# STM32F103C8T6_Coreboard.net
KiCad netlist of a schematic drawn in Altium Designer
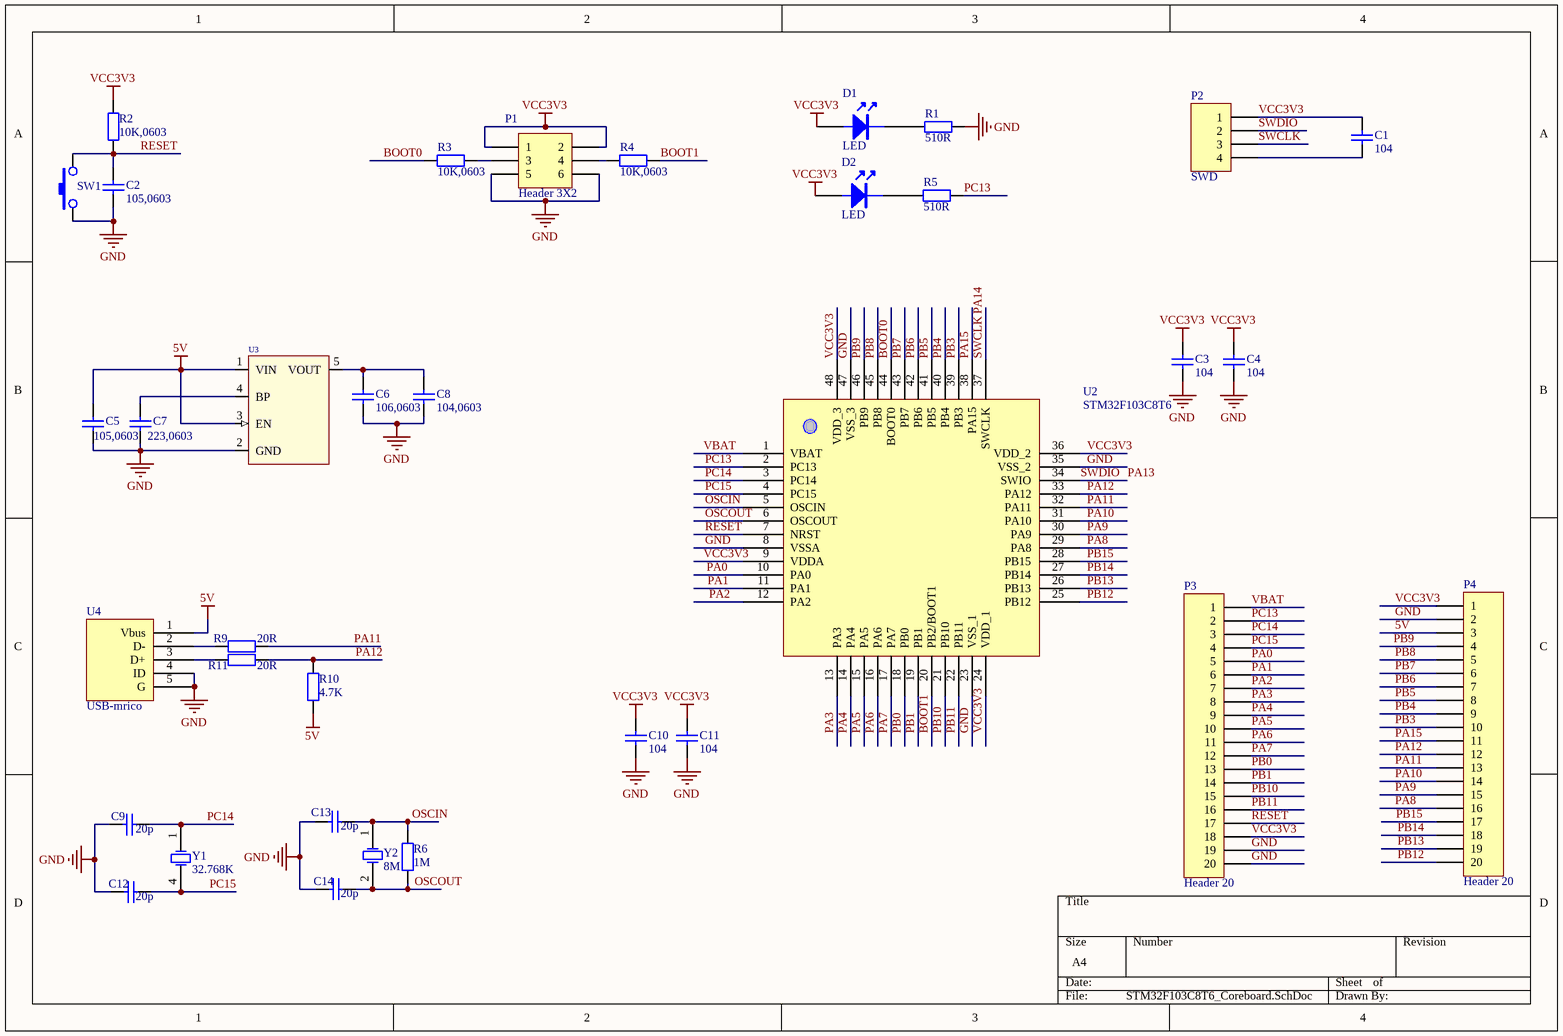
[diagram p0: STM32F103C8T6_Coreboard.SchDoc]

(export (version "E")
  (design (tool "Eeschema 10.0.6"))
  (components
    (comp (ref "C1")
      (value "104")
      (footprint "C0603")
      (description "Capacitor")
      (fields (field (name "PUBLISHER") "Altium Limited"))
      (libsource (lib "STM32F103C8T6_Coreboard") (part "Cap"))
    )
    (comp (ref "C2")
      (value "105,0603")
      (footprint "C0603")
      (description "Capacitor")
      (fields (field (name "PUBLISHER") "Altium Limited"))
      (libsource (lib "STM32F103C8T6_Coreboard") (part "Cap"))
    )
    (comp (ref "C3")
      (value "104")
      (footprint "C0603")
      (description "Capacitor")
      (fields (field (name "PUBLISHER") "Altium Limited"))
      (libsource (lib "STM32F103C8T6_Coreboard") (part "Cap"))
    )
    (comp (ref "C4")
      (value "104")
      (footprint "C0603")
      (description "Capacitor")
      (fields (field (name "PUBLISHER") "Altium Limited"))
      (libsource (lib "STM32F103C8T6_Coreboard") (part "Cap"))
    )
    (comp (ref "C5")
      (value "105,0603")
      (footprint "C0603")
      (description "Capacitor")
      (fields (field (name "PUBLISHER") "Altium Limited"))
      (libsource (lib "STM32F103C8T6_Coreboard") (part "Cap"))
    )
    (comp (ref "C6")
      (value "106,0603")
      (footprint "C0603")
      (description "Capacitor")
      (fields (field (name "PUBLISHER") "Altium Limited"))
      (libsource (lib "STM32F103C8T6_Coreboard") (part "Cap"))
    )
    (comp (ref "C7")
      (value "223,0603")
      (footprint "C0603")
      (description "Capacitor")
      (fields (field (name "PUBLISHER") "Altium Limited"))
      (libsource (lib "STM32F103C8T6_Coreboard") (part "Cap"))
    )
    (comp (ref "C8")
      (value "104,0603")
      (footprint "C0603")
      (description "Capacitor")
      (fields (field (name "PUBLISHER") "Altium Limited"))
      (libsource (lib "STM32F103C8T6_Coreboard") (part "Cap"))
    )
    (comp (ref "C9")
      (value "20p")
      (footprint "C0603")
      (description "Capacitor")
      (fields (field (name "PUBLISHER") "Altium Limited"))
      (libsource (lib "STM32F103C8T6_Coreboard") (part "Cap"))
    )
    (comp (ref "C10")
      (value "104")
      (footprint "C0603")
      (description "Capacitor")
      (fields (field (name "PUBLISHER") "Altium Limited"))
      (libsource (lib "STM32F103C8T6_Coreboard") (part "Cap"))
    )
    (comp (ref "C11")
      (value "104")
      (footprint "C0603")
      (description "Capacitor")
      (fields (field (name "PUBLISHER") "Altium Limited"))
      (libsource (lib "STM32F103C8T6_Coreboard") (part "Cap"))
    )
    (comp (ref "C12")
      (value "20p")
      (footprint "C0603")
      (description "Capacitor")
      (fields (field (name "PUBLISHER") "Altium Limited"))
      (libsource (lib "STM32F103C8T6_Coreboard") (part "Cap"))
    )
    (comp (ref "C13")
      (value "20p")
      (footprint "C0603")
      (description "Capacitor")
      (fields (field (name "PUBLISHER") "Altium Limited"))
      (libsource (lib "STM32F103C8T6_Coreboard") (part "Cap"))
    )
    (comp (ref "C14")
      (value "20p")
      (footprint "C0603")
      (description "Capacitor")
      (fields (field (name "PUBLISHER") "Altium Limited"))
      (libsource (lib "STM32F103C8T6_Coreboard") (part "Cap"))
    )
    (comp (ref "D1") (value "LED") (footprint "LED") (libsource (lib "STM32F103C8T6_Coreboard") (part "LED")))
    (comp (ref "D2") (value "LED") (footprint "LED") (libsource (lib "STM32F103C8T6_Coreboard") (part "LED")))
    (comp (ref "P1")
      (value "Header 3X2")
      (footprint "HDR2X3")
      (description "Header, 3-Pin, Dual row")
      (fields (field (name "PUBLISHER") "Altium Limited"))
      (libsource (lib "STM32F103C8T6_Coreboard") (part "Header 3X2"))
    )
    (comp (ref "P2")
      (value "SWD")
      (footprint "HDR1X4H")
      (description "Header, 4-Pin")
      (fields (field (name "PUBLISHER") "Altium Limited"))
      (libsource (lib "STM32F103C8T6_Coreboard") (part "Header 4"))
    )
    (comp (ref "P3")
      (value "Header 20")
      (footprint "HDR1X20")
      (description "Header, 20-Pin")
      (fields (field (name "PUBLISHER") "Altium Limited"))
      (libsource (lib "") (part "Header 20_1"))
    )
    (comp (ref "P4")
      (value "Header 20")
      (footprint "HDR1X20")
      (description "Header, 20-Pin")
      (fields (field (name "PUBLISHER") "Altium Limited"))
      (libsource (lib "STM32F103C8T6_Coreboard") (part "Header 20"))
    )
    (comp (ref "R1")
      (value "510R")
      (footprint "R0603")
      (description "Resistor")
      (fields (field (name "PUBLISHER") "Altium Limited"))
      (libsource (lib "STM32F103C8T6_Coreboard") (part "Res2"))
    )
    (comp (ref "R2")
      (value "10K,0603")
      (footprint "R0603")
      (description "Resistor")
      (fields (field (name "PUBLISHER") "Altium Limited"))
      (libsource (lib "") (part "Res2_1"))
    )
    (comp (ref "R3")
      (value "10K,0603")
      (footprint "R0603")
      (description "Resistor")
      (fields (field (name "PUBLISHER") "Altium Limited"))
      (libsource (lib "STM32F103C8T6_Coreboard") (part "Res2"))
    )
    (comp (ref "R4")
      (value "10K,0603")
      (footprint "R0603")
      (description "Resistor")
      (fields (field (name "PUBLISHER") "Altium Limited"))
      (libsource (lib "STM32F103C8T6_Coreboard") (part "Res2"))
    )
    (comp (ref "R5")
      (value "510R")
      (footprint "R0603")
      (description "Resistor")
      (fields (field (name "PUBLISHER") "Altium Limited"))
      (libsource (lib "STM32F103C8T6_Coreboard") (part "Res2"))
    )
    (comp (ref "R6")
      (value "1M")
      (footprint "R0603")
      (description "Resistor")
      (fields (field (name "PUBLISHER") "Altium Limited"))
      (libsource (lib "") (part "Res2_1"))
    )
    (comp (ref "R9")
      (value "20R")
      (footprint "R0603")
      (description "Resistor")
      (fields (field (name "PUBLISHER") "Altium Limited"))
      (libsource (lib "STM32F103C8T6_Coreboard") (part "Res2"))
    )
    (comp (ref "R10")
      (value "4.7K")
      (footprint "R0603")
      (description "Resistor")
      (fields (field (name "PUBLISHER") "Altium Limited"))
      (libsource (lib "") (part "Res2_1"))
    )
    (comp (ref "R11")
      (value "20R")
      (footprint "R0603")
      (description "Resistor")
      (fields (field (name "PUBLISHER") "Altium Limited"))
      (libsource (lib "STM32F103C8T6_Coreboard") (part "Res2"))
    )
    (comp (ref "SW1")
      (value "SW-PB_V")
      (footprint "KEY-SMT")
      (description "SWITCH")
      (libsource (lib "STM32F103C8T6_Coreboard") (part "SW-PB_V"))
    )
    (comp (ref "U2")
      (value "STM32F103C8T6")
      (footprint "48P")
      (libsource (lib "STM32F103C8T6_Coreboard") (part "STM32F103C8T6"))
    )
    (comp (ref "U3")
      (value "RT9193")
      (fields (field (name "ICA_PARTNUM") "$$2191094$$RT9193-15CU5") (field (name "PART NUMBER") "TMP-13"))
      (libsource (lib "STM32F103C8T6_Coreboard") (part "RT9193X_5P"))
    )
    (comp (ref "U4")
      (value "USB-mrico")
      (footprint "Micro_USB")
      (libsource (lib "STM32F103C8T6_Coreboard") (part "usb-STM"))
    )
    (comp (ref "Y1")
      (value "32.768K")
      (footprint "MC-306")
      (description "Crystal Oscillator")
      (fields (field (name "PUBLISHER") "Altium Limited"))
      (libsource (lib "STM32F103C8T6_Coreboard") (part "XTAL"))
    )
    (comp (ref "Y2")
      (value "8M")
      (footprint "XTAL1")
      (description "Crystal Oscillator")
      (fields (field (name "PUBLISHER") "Altium Limited"))
      (libsource (lib "STM32F103C8T6_Coreboard") (part "XTAL1"))
    )
  )
  (nets
    (net (code "1") (name "/BOOT0") (class "Default")
      (node (ref "R3") (pin "1") (pinfunction "1_1") (pintype "passive"))
      (node (ref "U2") (pin "44") (pinfunction "BOOT0_44") (pintype "passive"))
    )
    (net (code "2") (name "/BOOT1") (class "Default")
      (node (ref "R4") (pin "2") (pinfunction "2_2") (pintype "passive"))
      (node (ref "U2") (pin "20") (pinfunction "PB2/BOOT1_20") (pintype "passive"))
    )
    (net (code "3") (name "/OSCIN") (class "Default")
      (node (ref "C13") (pin "2") (pinfunction "2_2") (pintype "passive"))
      (node (ref "R6") (pin "2") (pinfunction "2_2") (pintype "passive"))
      (node (ref "U2") (pin "5") (pinfunction "OSCIN_5") (pintype "passive"))
      (node (ref "Y2") (pin "1") (pinfunction "OSC1_1") (pintype "passive"))
    )
    (net (code "4") (name "/OSCOUT") (class "Default")
      (node (ref "C14") (pin "2") (pinfunction "2_2") (pintype "passive"))
      (node (ref "R6") (pin "1") (pinfunction "1_1") (pintype "passive"))
      (node (ref "U2") (pin "6") (pinfunction "OSCOUT_6") (pintype "passive"))
      (node (ref "Y2") (pin "2") (pinfunction "OSC2_2") (pintype "passive"))
    )
    (net (code "5") (name "/PA0") (class "Default")
      (node (ref "P3") (pin "5") (pinfunction "5_5") (pintype "passive"))
      (node (ref "U2") (pin "10") (pinfunction "PA0_10") (pintype "passive"))
    )
    (net (code "6") (name "/PA1") (class "Default")
      (node (ref "P3") (pin "6") (pinfunction "6_6") (pintype "passive"))
      (node (ref "U2") (pin "11") (pinfunction "PA1_11") (pintype "passive"))
    )
    (net (code "7") (name "/PA2") (class "Default")
      (node (ref "P3") (pin "7") (pinfunction "7_7") (pintype "passive"))
      (node (ref "U2") (pin "12") (pinfunction "PA2_12") (pintype "passive"))
    )
    (net (code "8") (name "/PA3") (class "Default")
      (node (ref "P3") (pin "8") (pinfunction "8_8") (pintype "passive"))
      (node (ref "U2") (pin "13") (pinfunction "PA3_13") (pintype "passive"))
    )
    (net (code "9") (name "/PA4") (class "Default")
      (node (ref "P3") (pin "9") (pinfunction "9_9") (pintype "passive"))
      (node (ref "U2") (pin "14") (pinfunction "PA4_14") (pintype "passive"))
    )
    (net (code "10") (name "/PA5") (class "Default")
      (node (ref "P3") (pin "10") (pinfunction "10_10") (pintype "passive"))
      (node (ref "U2") (pin "15") (pinfunction "PA5_15") (pintype "passive"))
    )
    (net (code "11") (name "/PA6") (class "Default")
      (node (ref "P3") (pin "11") (pinfunction "11_11") (pintype "passive"))
      (node (ref "U2") (pin "16") (pinfunction "PA6_16") (pintype "passive"))
    )
    (net (code "12") (name "/PA7") (class "Default")
      (node (ref "P3") (pin "12") (pinfunction "12_12") (pintype "passive"))
      (node (ref "U2") (pin "17") (pinfunction "PA7_17") (pintype "passive"))
    )
    (net (code "13") (name "/PA8") (class "Default")
      (node (ref "P4") (pin "16") (pinfunction "16_16") (pintype "passive"))
      (node (ref "U2") (pin "29") (pinfunction "PA8_29") (pintype "passive"))
    )
    (net (code "14") (name "/PA9") (class "Default")
      (node (ref "P4") (pin "15") (pinfunction "15_15") (pintype "passive"))
      (node (ref "U2") (pin "30") (pinfunction "PA9_30") (pintype "passive"))
    )
    (net (code "15") (name "/PA10") (class "Default")
      (node (ref "P4") (pin "14") (pinfunction "14_14") (pintype "passive"))
      (node (ref "U2") (pin "31") (pinfunction "PA10_31") (pintype "passive"))
    )
    (net (code "16") (name "/PA11") (class "Default")
      (node (ref "P4") (pin "13") (pinfunction "13_13") (pintype "passive"))
      (node (ref "R9") (pin "2") (pinfunction "2_2") (pintype "passive"))
      (node (ref "U2") (pin "32") (pinfunction "PA11_32") (pintype "passive"))
    )
    (net (code "17") (name "/PA12") (class "Default")
      (node (ref "P4") (pin "12") (pinfunction "12_12") (pintype "passive"))
      (node (ref "R10") (pin "2") (pinfunction "2_2") (pintype "passive"))
      (node (ref "R11") (pin "2") (pinfunction "2_2") (pintype "passive"))
      (node (ref "U2") (pin "33") (pinfunction "PA12_33") (pintype "passive"))
    )
    (net (code "18") (name "/PA13") (class "Default")
      (node (ref "P2") (pin "2") (pinfunction "2_2") (pintype "passive"))
      (node (ref "U2") (pin "34") (pinfunction "SWIO_34") (pintype "passive"))
    )
    (net (code "19") (name "/PA14") (class "Default")
      (node (ref "P2") (pin "3") (pinfunction "3_3") (pintype "passive"))
      (node (ref "U2") (pin "37") (pinfunction "SWCLK_37") (pintype "passive"))
    )
    (net (code "20") (name "/PA15") (class "Default")
      (node (ref "P4") (pin "11") (pinfunction "11_11") (pintype "passive"))
      (node (ref "U2") (pin "38") (pinfunction "PA15_38") (pintype "passive"))
    )
    (net (code "21") (name "/PB0") (class "Default")
      (node (ref "P3") (pin "13") (pinfunction "13_13") (pintype "passive"))
      (node (ref "U2") (pin "18") (pinfunction "PB0_18") (pintype "passive"))
    )
    (net (code "22") (name "/PB1") (class "Default")
      (node (ref "P3") (pin "14") (pinfunction "14_14") (pintype "passive"))
      (node (ref "U2") (pin "19") (pinfunction "PB1_19") (pintype "passive"))
    )
    (net (code "23") (name "/PB3") (class "Default")
      (node (ref "P4") (pin "10") (pinfunction "10_10") (pintype "passive"))
      (node (ref "U2") (pin "39") (pinfunction "PB3_39") (pintype "passive"))
    )
    (net (code "24") (name "/PB4") (class "Default")
      (node (ref "P4") (pin "9") (pinfunction "9_9") (pintype "passive"))
      (node (ref "U2") (pin "40") (pinfunction "PB4_40") (pintype "passive"))
    )
    (net (code "25") (name "/PB5") (class "Default")
      (node (ref "P4") (pin "8") (pinfunction "8_8") (pintype "passive"))
      (node (ref "U2") (pin "41") (pinfunction "PB5_41") (pintype "passive"))
    )
    (net (code "26") (name "/PB6") (class "Default")
      (node (ref "P4") (pin "7") (pinfunction "7_7") (pintype "passive"))
      (node (ref "U2") (pin "42") (pinfunction "PB6_42") (pintype "passive"))
    )
    (net (code "27") (name "/PB7") (class "Default")
      (node (ref "P4") (pin "6") (pinfunction "6_6") (pintype "passive"))
      (node (ref "U2") (pin "43") (pinfunction "PB7_43") (pintype "passive"))
    )
    (net (code "28") (name "/PB8") (class "Default")
      (node (ref "P4") (pin "5") (pinfunction "5_5") (pintype "passive"))
      (node (ref "U2") (pin "45") (pinfunction "PB8_45") (pintype "passive"))
    )
    (net (code "29") (name "/PB9") (class "Default")
      (node (ref "P4") (pin "4") (pinfunction "4_4") (pintype "passive"))
      (node (ref "U2") (pin "46") (pinfunction "PB9_46") (pintype "passive"))
    )
    (net (code "30") (name "/PB10") (class "Default")
      (node (ref "P3") (pin "15") (pinfunction "15_15") (pintype "passive"))
      (node (ref "U2") (pin "21") (pinfunction "PB10_21") (pintype "passive"))
    )
    (net (code "31") (name "/PB11") (class "Default")
      (node (ref "P3") (pin "16") (pinfunction "16_16") (pintype "passive"))
      (node (ref "U2") (pin "22") (pinfunction "PB11_22") (pintype "passive"))
    )
    (net (code "32") (name "/PB12") (class "Default")
      (node (ref "P4") (pin "20") (pinfunction "20_20") (pintype "passive"))
      (node (ref "U2") (pin "25") (pinfunction "PB12_25") (pintype "passive"))
    )
    (net (code "33") (name "/PB13") (class "Default")
      (node (ref "P4") (pin "19") (pinfunction "19_19") (pintype "passive"))
      (node (ref "U2") (pin "26") (pinfunction "PB13_26") (pintype "passive"))
    )
    (net (code "34") (name "/PB14") (class "Default")
      (node (ref "P4") (pin "18") (pinfunction "18_18") (pintype "passive"))
      (node (ref "U2") (pin "27") (pinfunction "PB14_27") (pintype "passive"))
    )
    (net (code "35") (name "/PB15") (class "Default")
      (node (ref "P4") (pin "17") (pinfunction "17_17") (pintype "passive"))
      (node (ref "U2") (pin "28") (pinfunction "PB15_28") (pintype "passive"))
    )
    (net (code "36") (name "/PC13") (class "Default")
      (node (ref "P3") (pin "2") (pinfunction "2_2") (pintype "passive"))
      (node (ref "R5") (pin "2") (pinfunction "2_2") (pintype "passive"))
      (node (ref "U2") (pin "2") (pinfunction "PC13_2") (pintype "passive"))
    )
    (net (code "37") (name "/PC14") (class "Default")
      (node (ref "C9") (pin "2") (pinfunction "2_2") (pintype "passive"))
      (node (ref "P3") (pin "3") (pinfunction "3_3") (pintype "passive"))
      (node (ref "U2") (pin "3") (pinfunction "PC14_3") (pintype "passive"))
      (node (ref "Y1") (pin "1") (pinfunction "OSC1_1") (pintype "passive"))
    )
    (net (code "38") (name "/PC15") (class "Default")
      (node (ref "C12") (pin "2") (pinfunction "2_2") (pintype "passive"))
      (node (ref "P3") (pin "4") (pinfunction "4_4") (pintype "passive"))
      (node (ref "U2") (pin "4") (pinfunction "PC15_4") (pintype "passive"))
      (node (ref "Y1") (pin "4") (pinfunction "OSC2_4") (pintype "passive"))
    )
    (net (code "39") (name "/RESET") (class "Default")
      (node (ref "C2") (pin "2") (pinfunction "2_2") (pintype "passive"))
      (node (ref "P3") (pin "17") (pinfunction "17_17") (pintype "passive"))
      (node (ref "R2") (pin "1") (pinfunction "1_1") (pintype "passive"))
      (node (ref "SW1") (pin "1") (pinfunction "1_1") (pintype "passive"))
      (node (ref "U2") (pin "7") (pinfunction "NRST_7") (pintype "passive"))
    )
    (net (code "40") (name "/VBAT") (class "Default")
      (node (ref "P3") (pin "1") (pinfunction "1_1") (pintype "passive"))
      (node (ref "U2") (pin "1") (pinfunction "VBAT_1") (pintype "passive"))
    )
    (net (code "41") (name "5V") (class "Default")
      (node (ref "C5") (pin "2") (pinfunction "2_2") (pintype "passive"))
      (node (ref "P4") (pin "3") (pinfunction "3_3") (pintype "passive"))
      (node (ref "R10") (pin "1") (pinfunction "1_1") (pintype "passive"))
      (node (ref "U3") (pin "1") (pinfunction "VIN_1") (pintype "power_in"))
      (node (ref "U3") (pin "3") (pinfunction "EN_3") (pintype "input"))
      (node (ref "U4") (pin "1") (pinfunction "Vbus_1") (pintype "passive"))
    )
    (net (code "42") (name "GND") (class "Default")
      (node (ref "C10") (pin "1") (pinfunction "1_1") (pintype "passive"))
      (node (ref "C11") (pin "1") (pinfunction "1_1") (pintype "passive"))
      (node (ref "C12") (pin "1") (pinfunction "1_1") (pintype "passive"))
      (node (ref "C13") (pin "1") (pinfunction "1_1") (pintype "passive"))
      (node (ref "C14") (pin "1") (pinfunction "1_1") (pintype "passive"))
      (node (ref "C2") (pin "1") (pinfunction "1_1") (pintype "passive"))
      (node (ref "C3") (pin "1") (pinfunction "1_1") (pintype "passive"))
      (node (ref "C4") (pin "1") (pinfunction "1_1") (pintype "passive"))
      (node (ref "C5") (pin "1") (pinfunction "1_1") (pintype "passive"))
      (node (ref "C6") (pin "1") (pinfunction "1_1") (pintype "passive"))
      (node (ref "C7") (pin "1") (pinfunction "1_1") (pintype "passive"))
      (node (ref "C8") (pin "1") (pinfunction "1_1") (pintype "passive"))
      (node (ref "C9") (pin "1") (pinfunction "1_1") (pintype "passive"))
      (node (ref "P1") (pin "5") (pinfunction "5_5") (pintype "passive"))
      (node (ref "P1") (pin "6") (pinfunction "6_6") (pintype "passive"))
      (node (ref "P3") (pin "19") (pinfunction "19_19") (pintype "passive"))
      (node (ref "P3") (pin "20") (pinfunction "20_20") (pintype "passive"))
      (node (ref "P4") (pin "2") (pinfunction "2_2") (pintype "passive"))
      (node (ref "R1") (pin "2") (pinfunction "2_2") (pintype "passive"))
      (node (ref "SW1") (pin "2") (pinfunction "2_2") (pintype "passive"))
      (node (ref "U2") (pin "23") (pinfunction "VSS_1_23") (pintype "passive"))
      (node (ref "U2") (pin "35") (pinfunction "VSS_2_35") (pintype "passive"))
      (node (ref "U2") (pin "47") (pinfunction "VSS_3_47") (pintype "passive"))
      (node (ref "U2") (pin "8") (pinfunction "VSSA_8") (pintype "passive"))
      (node (ref "U3") (pin "2") (pinfunction "GND_2") (pintype "power_in"))
      (node (ref "U4") (pin "4") (pinfunction "ID_4") (pintype "passive"))
      (node (ref "U4") (pin "5") (pinfunction "G_5") (pintype "passive"))
    )
    (net (code "43") (name "Net-(C1-Pad1)") (class "Default")
      (node (ref "C1") (pin "1") (pinfunction "1_1") (pintype "passive"))
      (node (ref "P2") (pin "4") (pinfunction "4_4") (pintype "passive"))
    )
    (net (code "44") (name "Net-(D1-2)") (class "Default")
      (node (ref "D1") (pin "K") (pinfunction "2_K") (pintype "passive"))
      (node (ref "R1") (pin "1") (pinfunction "1_1") (pintype "passive"))
    )
    (net (code "45") (name "Net-(D2-2)") (class "Default")
      (node (ref "D2") (pin "K") (pinfunction "2_K") (pintype "passive"))
      (node (ref "R5") (pin "1") (pinfunction "1_1") (pintype "passive"))
    )
    (net (code "46") (name "Net-(P1-Pad3)") (class "Default")
      (node (ref "P1") (pin "3") (pinfunction "3_3") (pintype "passive"))
      (node (ref "R3") (pin "2") (pinfunction "2_2") (pintype "passive"))
    )
    (net (code "47") (name "Net-(P1-Pad4)") (class "Default")
      (node (ref "P1") (pin "4") (pinfunction "4_4") (pintype "passive"))
      (node (ref "R4") (pin "1") (pinfunction "1_1") (pintype "passive"))
    )
    (net (code "48") (name "Net-(U3-BP)") (class "Default")
      (node (ref "C7") (pin "2") (pinfunction "2_2") (pintype "passive"))
      (node (ref "U3") (pin "4") (pinfunction "BP_4") (pintype "passive"))
    )
    (net (code "49") (name "Net-(U3-VOUT)") (class "Default")
      (node (ref "C6") (pin "2") (pinfunction "2_2") (pintype "passive"))
      (node (ref "C8") (pin "2") (pinfunction "2_2") (pintype "passive"))
      (node (ref "U3") (pin "5") (pinfunction "VOUT_5") (pintype "power_in"))
    )
    (net (code "50") (name "Net-(U4-D+)") (class "Default")
      (node (ref "R11") (pin "1") (pinfunction "1_1") (pintype "passive"))
      (node (ref "U4") (pin "3") (pinfunction "D+_3") (pintype "passive"))
    )
    (net (code "51") (name "Net-(U4-D-)") (class "Default")
      (node (ref "R9") (pin "1") (pinfunction "1_1") (pintype "passive"))
      (node (ref "U4") (pin "2") (pinfunction "D-_2") (pintype "passive"))
    )
    (net (code "52") (name "VCC3V3") (class "Default")
      (node (ref "C1") (pin "2") (pinfunction "2_2") (pintype "passive"))
      (node (ref "C10") (pin "2") (pinfunction "2_2") (pintype "passive"))
      (node (ref "C11") (pin "2") (pinfunction "2_2") (pintype "passive"))
      (node (ref "C3") (pin "2") (pinfunction "2_2") (pintype "passive"))
      (node (ref "C4") (pin "2") (pinfunction "2_2") (pintype "passive"))
      (node (ref "D1") (pin "A") (pinfunction "1_A") (pintype "passive"))
      (node (ref "D2") (pin "A") (pinfunction "1_A") (pintype "passive"))
      (node (ref "P1") (pin "1") (pinfunction "1_1") (pintype "passive"))
      (node (ref "P1") (pin "2") (pinfunction "2_2") (pintype "passive"))
      (node (ref "P2") (pin "1") (pinfunction "1_1") (pintype "passive"))
      (node (ref "P3") (pin "18") (pinfunction "18_18") (pintype "passive"))
      (node (ref "P4") (pin "1") (pinfunction "1_1") (pintype "passive"))
      (node (ref "R2") (pin "2") (pinfunction "2_2") (pintype "passive"))
      (node (ref "U2") (pin "24") (pinfunction "VDD_1_24") (pintype "passive"))
      (node (ref "U2") (pin "36") (pinfunction "VDD_2_36") (pintype "passive"))
      (node (ref "U2") (pin "48") (pinfunction "VDD_3_48") (pintype "passive"))
      (node (ref "U2") (pin "9") (pinfunction "VDDA_9") (pintype "passive"))
    )
  )
)
